# Qwiic_MultiStar.net
KiCad netlist of a schematic drawn in EAGLE
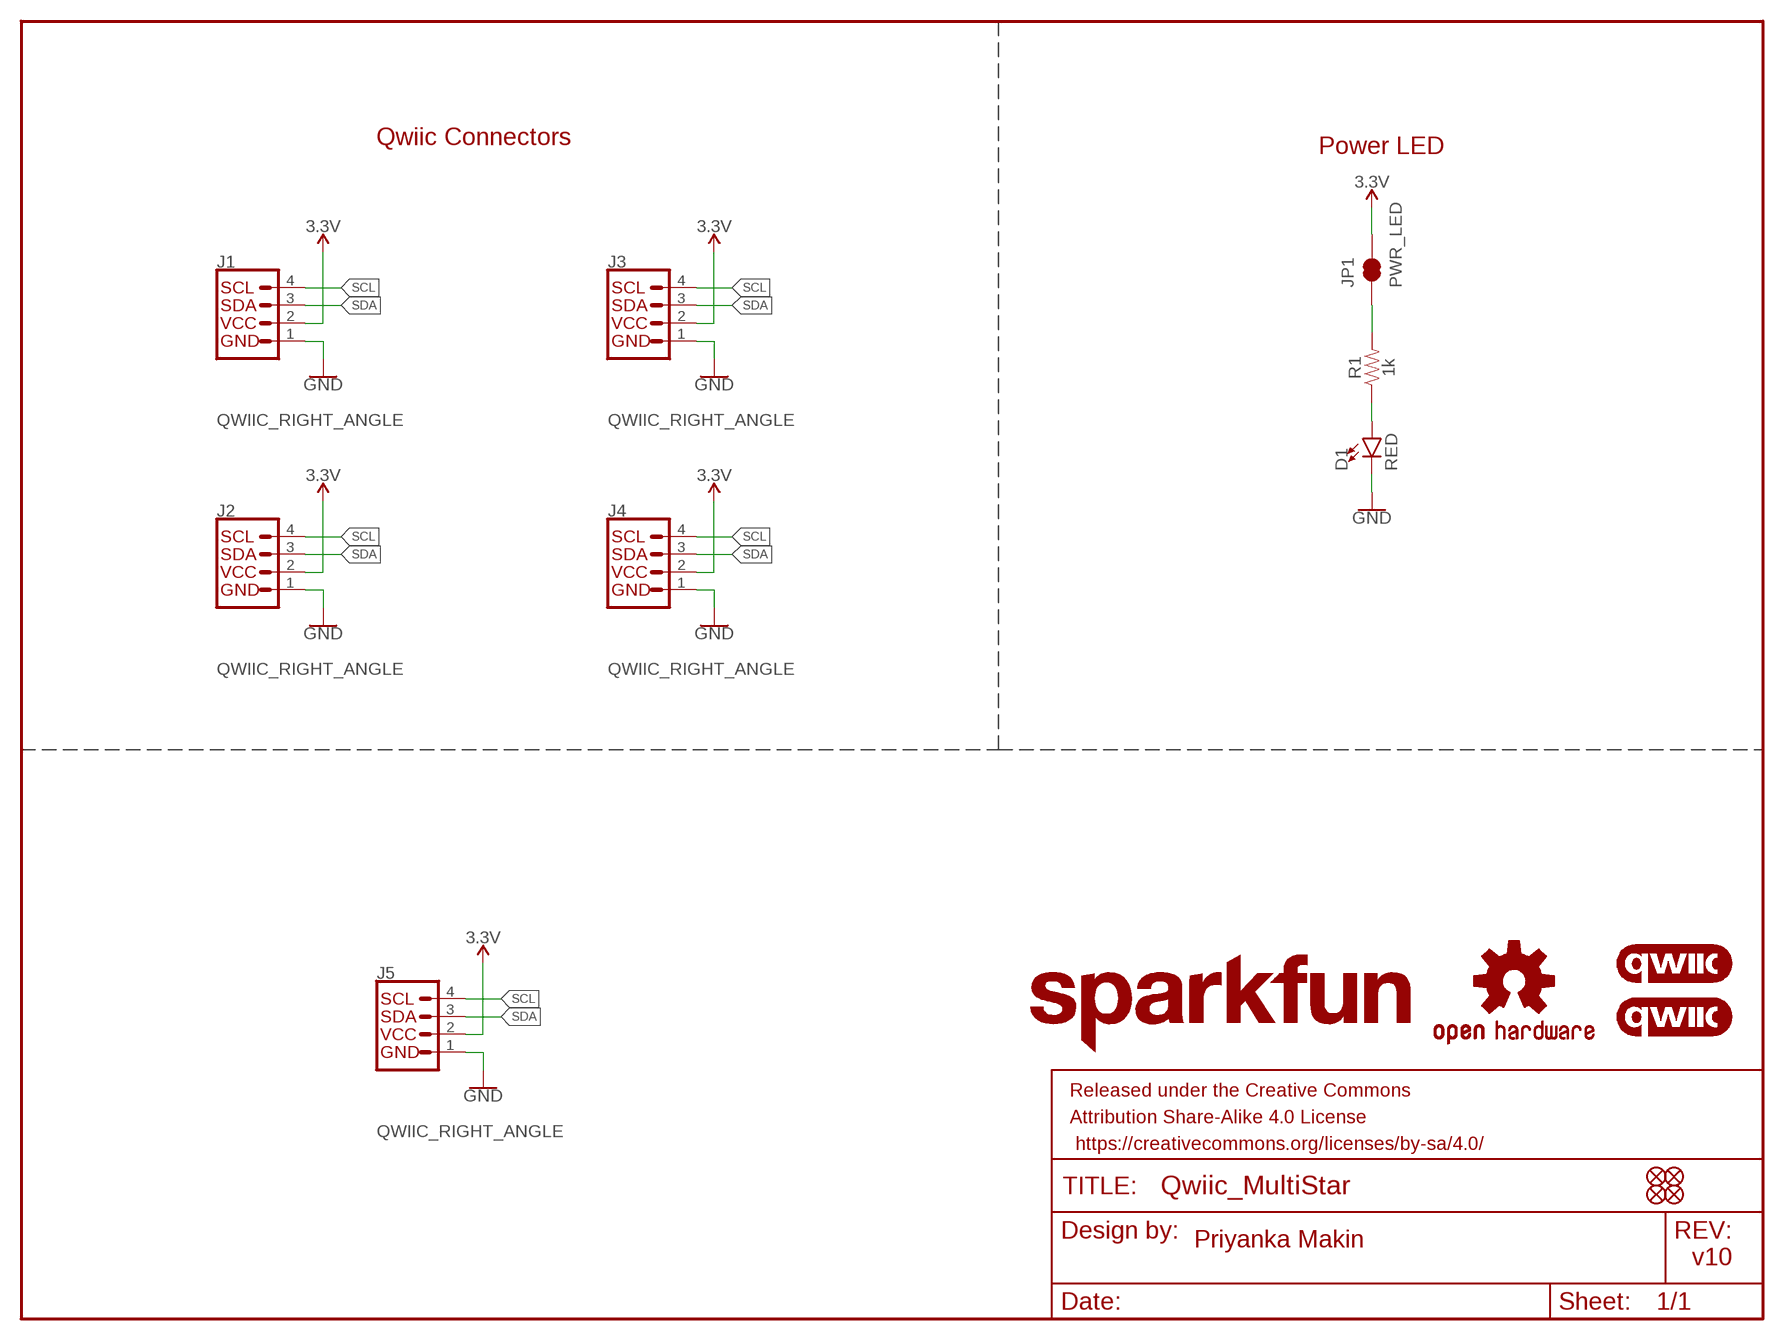
[diagram p0: schematic, sheet 1]

(export (version "E")
  (design (tool "Eeschema 10.0.6"))
  (components
    (comp (ref "D1")
      (value "RED")
      (footprint "eagle-import:LED-0603")
      (libsource (lib "eagle-import") (part "LED-RED0603"))
    )
    (comp (ref "FD1")
      (value "FIDUCIAL1X2")
      (footprint "eagle-import:FIDUCIAL-1X2")
      (libsource (lib "eagle-import") (part "FIDUCIAL1X2"))
    )
    (comp (ref "FD2")
      (value "FIDUCIAL1X2")
      (footprint "eagle-import:FIDUCIAL-1X2")
      (libsource (lib "eagle-import") (part "FIDUCIAL1X2"))
    )
    (comp (ref "FD3")
      (value "FIDUCIAL1X2")
      (footprint "eagle-import:FIDUCIAL-1X2")
      (libsource (lib "eagle-import") (part "FIDUCIAL1X2"))
    )
    (comp (ref "FD4")
      (value "FIDUCIAL1X2")
      (footprint "eagle-import:FIDUCIAL-1X2")
      (libsource (lib "eagle-import") (part "FIDUCIAL1X2"))
    )
    (comp (ref "FRAME1")
      (value "FRAME-LETTER")
      (footprint "eagle-import:CREATIVE_COMMONS")
      (libsource (lib "eagle-import") (part "FRAME-LETTER"))
    )
    (comp (ref "J1")
      (value "QWIIC_RIGHT_ANGLE")
      (footprint "eagle-import:JST04_1MM_RA")
      (libsource (lib "eagle-import") (part "QWIIC_CONNECTORJS-1MM"))
    )
    (comp (ref "J2")
      (value "QWIIC_RIGHT_ANGLE")
      (footprint "eagle-import:JST04_1MM_RA")
      (libsource (lib "eagle-import") (part "QWIIC_CONNECTORJS-1MM"))
    )
    (comp (ref "J3")
      (value "QWIIC_RIGHT_ANGLE")
      (footprint "eagle-import:JST04_1MM_RA")
      (libsource (lib "eagle-import") (part "QWIIC_CONNECTORJS-1MM"))
    )
    (comp (ref "J4")
      (value "QWIIC_RIGHT_ANGLE")
      (footprint "eagle-import:JST04_1MM_RA")
      (libsource (lib "eagle-import") (part "QWIIC_CONNECTORJS-1MM"))
    )
    (comp (ref "J5")
      (value "QWIIC_RIGHT_ANGLE")
      (footprint "eagle-import:JST04_1MM_RA")
      (libsource (lib "eagle-import") (part "QWIIC_CONNECTORJS-1MM"))
    )
    (comp (ref "JP1")
      (value "PWR_LED")
      (footprint "eagle-import:SMT-JUMPER_2_NC_TRACE_SILK")
      (libsource (lib "eagle-import") (part "JUMPER-SMT_2_NC_TRACE_SILK"))
    )
    (comp (ref "LOGO1")
      (value "QWIIC_LOGO_5MM")
      (footprint "eagle-import:QWIIC_5MM")
      (libsource (lib "eagle-import") (part "QWIIC_LOGO_5MM"))
    )
    (comp (ref "LOGO2")
      (value "QWIIC_LOGO_5MM")
      (footprint "eagle-import:QWIIC_5MM")
      (libsource (lib "eagle-import") (part "QWIIC_LOGO_5MM"))
    )
    (comp (ref "LOGO3")
      (value "OSHW-LOGOS")
      (footprint "eagle-import:OSHW-LOGO-S")
      (libsource (lib "eagle-import") (part "OSHW-LOGOS"))
    )
    (comp (ref "LOGO4")
      (value "SFE_LOGO_NAME.2_INCH")
      (footprint "eagle-import:SFE_LOGO_NAME_.2")
      (libsource (lib "eagle-import") (part "SFE_LOGO_NAME.2_INCH"))
    )
    (comp (ref "R1")
      (value "1k")
      (footprint "eagle-import:0603")
      (libsource (lib "eagle-import") (part "1KOHM-0603-1/10W-1%"))
    )
  )
  (nets
    (net (code "1") (name "3.3V") (class "Default")
      (node (ref "J1") (pin "2") (pinfunction "2_2") (pintype "power_in"))
      (node (ref "J2") (pin "2") (pinfunction "2_2") (pintype "power_in"))
      (node (ref "J3") (pin "2") (pinfunction "2_2") (pintype "power_in"))
      (node (ref "J4") (pin "2") (pinfunction "2_2") (pintype "power_in"))
      (node (ref "J5") (pin "2") (pinfunction "2_2") (pintype "power_in"))
      (node (ref "JP1") (pin "2") (pinfunction "2_2") (pintype "passive"))
    )
    (net (code "2") (name "GND") (class "Default")
      (node (ref "D1") (pin "C") (pinfunction "C_C") (pintype "passive"))
      (node (ref "J1") (pin "1") (pinfunction "1_1") (pintype "power_in"))
      (node (ref "J2") (pin "1") (pinfunction "1_1") (pintype "power_in"))
      (node (ref "J3") (pin "1") (pinfunction "1_1") (pintype "power_in"))
      (node (ref "J4") (pin "1") (pinfunction "1_1") (pintype "power_in"))
      (node (ref "J5") (pin "1") (pinfunction "1_1") (pintype "power_in"))
    )
    (net (code "3") (name "Net-(D1-PadA)") (class "Default")
      (node (ref "D1") (pin "A") (pinfunction "A_A") (pintype "passive"))
      (node (ref "R1") (pin "1") (pinfunction "1_1") (pintype "passive"))
    )
    (net (code "4") (name "Net-(JP1-Pad1)") (class "Default")
      (node (ref "JP1") (pin "1") (pinfunction "1_1") (pintype "passive"))
      (node (ref "R1") (pin "2") (pinfunction "2_2") (pintype "passive"))
    )
    (net (code "5") (name "SCL") (class "Default")
      (node (ref "J1") (pin "4") (pinfunction "4_4") (pintype "passive"))
      (node (ref "J2") (pin "4") (pinfunction "4_4") (pintype "passive"))
      (node (ref "J3") (pin "4") (pinfunction "4_4") (pintype "passive"))
      (node (ref "J4") (pin "4") (pinfunction "4_4") (pintype "passive"))
      (node (ref "J5") (pin "4") (pinfunction "4_4") (pintype "passive"))
    )
    (net (code "6") (name "SDA") (class "Default")
      (node (ref "J1") (pin "3") (pinfunction "3_3") (pintype "passive"))
      (node (ref "J2") (pin "3") (pinfunction "3_3") (pintype "passive"))
      (node (ref "J3") (pin "3") (pinfunction "3_3") (pintype "passive"))
      (node (ref "J4") (pin "3") (pinfunction "3_3") (pintype "passive"))
      (node (ref "J5") (pin "3") (pinfunction "3_3") (pintype "passive"))
    )
  )
)
